# NDS-JOYSTICK.net
KiCad netlist of a schematic drawn in EAGLE
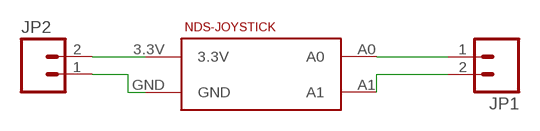
[diagram p0: schematic, sheet 1]

(export (version "E")
  (design (tool "Eeschema 10.0.6"))
  (components
    (comp (ref "JP1")
      (value "M02LOCK")
      (footprint "eagle-import:1X02_LOCK")
      (libsource (lib "eagle-import") (part "M02LOCK"))
    )
    (comp (ref "JP2")
      (value "M02LOCK")
      (footprint "eagle-import:1X02_LOCK")
      (libsource (lib "eagle-import") (part "M02LOCK"))
    )
    (comp (ref "U$1")
      (value "NDS-JOYSTICK")
      (footprint "eagle-import:NDS-JOYSTICK")
      (libsource (lib "eagle-import") (part "NDS-JOYSTICK"))
    )
  )
  (nets
    (net (code "1") (name "Net-(JP1-Pad1)") (class "Default")
      (node (ref "JP1") (pin "1") (pinfunction "1_1") (pintype "passive"))
      (node (ref "U$1") (pin "A0") (pinfunction "A0_A0") (pintype "bidirectional"))
    )
    (net (code "2") (name "Net-(JP1-Pad2)") (class "Default")
      (node (ref "JP1") (pin "2") (pinfunction "2_2") (pintype "passive"))
      (node (ref "U$1") (pin "A1") (pinfunction "A1_A1") (pintype "bidirectional"))
    )
    (net (code "3") (name "Net-(JP2-Pad1)") (class "Default")
      (node (ref "JP2") (pin "1") (pinfunction "1_1") (pintype "passive"))
      (node (ref "U$1") (pin "GND") (pinfunction "GND_GND") (pintype "bidirectional"))
    )
    (net (code "4") (name "Net-(JP2-Pad2)") (class "Default")
      (node (ref "JP2") (pin "2") (pinfunction "2_2") (pintype "passive"))
      (node (ref "U$1") (pin "3.3V") (pinfunction "3.3V_3.3V") (pintype "bidirectional"))
    )
  )
)
